# mainboard_motor_v1_4.net
KiCad netlist of a schematic drawn in Altium Designer
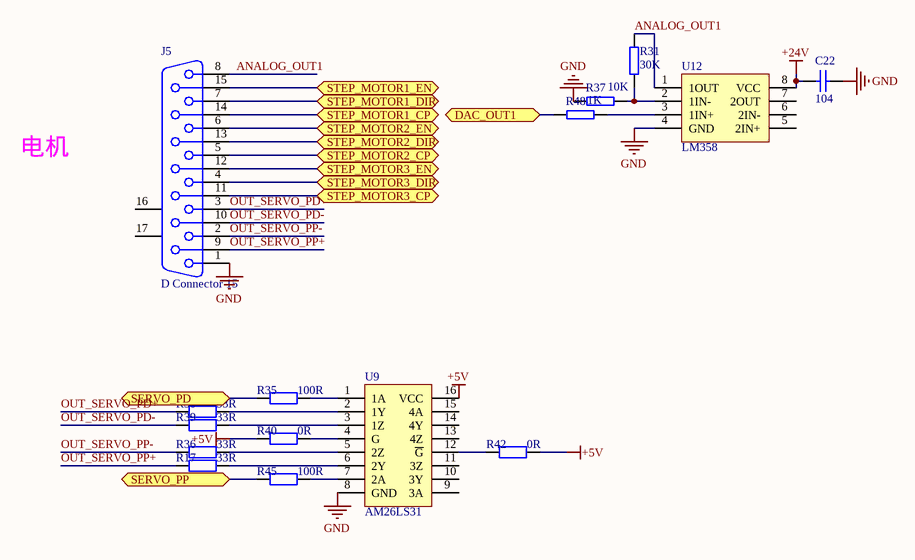
[diagram p0: mainboard_motor.v1.4.SchDoc]

(export (version "E")
  (design (tool "Eeschema 10.0.6"))
  (components
    (comp (ref "C22")
      (value "104")
      (footprint "0805")
      (description "Capacitor")
      (fields (field (name "PUBLISHER") "Altium Limited"))
      (libsource (lib "TIAN's Schlib") (part "Cap"))
    )
    (comp (ref "J5")
      (value "D Connector 15")
      (footprint "DSUB1.385-2H15")
      (description "Receptacle Assembly, 15 Position, Right Angle")
      (fields (field (name "PUBLISHER") "Altium Limited"))
      (libsource (lib "Miscellaneous Connectors") (part "D Connector 15"))
    )
    (comp (ref "R17")
      (value "33R")
      (footprint "0805")
      (description "Resistor")
      (fields (field (name "PUBLISHER") "Altium Limited"))
      (libsource (lib "TIAN's Schlib") (part "Res2"))
    )
    (comp (ref "R31")
      (value "30K")
      (footprint "0805")
      (description "电阻")
      (libsource (lib "Component") (part "RES"))
    )
    (comp (ref "R35")
      (value "100R")
      (footprint "0805")
      (description "Resistor")
      (fields (field (name "PUBLISHER") "Altium Limited"))
      (libsource (lib "TIAN's Schlib") (part "Res2"))
    )
    (comp (ref "R36")
      (value "33R")
      (footprint "0805")
      (description "Resistor")
      (fields (field (name "PUBLISHER") "Altium Limited"))
      (libsource (lib "TIAN's Schlib") (part "Res2"))
    )
    (comp (ref "R37")
      (value "10K")
      (footprint "0805")
      (description "电阻")
      (libsource (lib "Component") (part "RES"))
    )
    (comp (ref "R38")
      (value "33R")
      (footprint "0805")
      (description "Resistor")
      (fields (field (name "PUBLISHER") "Altium Limited"))
      (libsource (lib "TIAN's Schlib") (part "Res2"))
    )
    (comp (ref "R39")
      (value "33R")
      (footprint "0805")
      (description "Resistor")
      (fields (field (name "PUBLISHER") "Altium Limited"))
      (libsource (lib "TIAN's Schlib") (part "Res2"))
    )
    (comp (ref "R40")
      (value "0R")
      (footprint "0805")
      (description "Resistor")
      (fields (field (name "PUBLISHER") "Altium Limited"))
      (libsource (lib "TIAN's Schlib") (part "Res2"))
    )
    (comp (ref "R42")
      (value "0R")
      (footprint "0805")
      (description "Resistor")
      (fields (field (name "PUBLISHER") "Altium Limited"))
      (libsource (lib "TIAN's Schlib") (part "Res2"))
    )
    (comp (ref "R45")
      (value "100R")
      (footprint "0805")
      (description "Resistor")
      (fields (field (name "PUBLISHER") "Altium Limited"))
      (libsource (lib "TIAN's Schlib") (part "Res2"))
    )
    (comp (ref "R48")
      (value "1K")
      (footprint "0805")
      (description "电阻")
      (libsource (lib "Component") (part "RES"))
    )
    (comp (ref "U9") (value "AM26LS31") (footprint "SO-16") (libsource (lib "Chip") (part "AM26LS31")))
    (comp (ref "U12") (value "LM358") (footprint "SO-8") (libsource (lib "Chip") (part "LM358")))
  )
  (nets
    (net (code "1") (name "+5V") (class "Default")
      (node (ref "R40") (pin "2") (pinfunction "2_2") (pintype "passive"))
      (node (ref "R42") (pin "1") (pinfunction "1_1") (pintype "passive"))
      (node (ref "U9") (pin "16") (pinfunction "VCC_16") (pintype "passive"))
    )
    (net (code "2") (name "+24V") (class "Default")
      (node (ref "C22") (pin "2") (pinfunction "2_2") (pintype "passive"))
      (node (ref "U12") (pin "8") (pinfunction "VCC_8") (pintype "passive"))
    )
    (net (code "3") (name "/ANALOG_OUT1") (class "Default")
      (node (ref "J5") (pin "8") (pinfunction "8_8") (pintype "passive"))
      (node (ref "R31") (pin "1") (pinfunction "1_1") (pintype "passive"))
      (node (ref "U12") (pin "1") (pinfunction "1OUT_1") (pintype "passive"))
    )
    (net (code "4") (name "/DAC_OUT1") (class "Default")
      (node (ref "R48") (pin "2") (pinfunction "2_2") (pintype "passive"))
    )
    (net (code "5") (name "/OUT_SERVO_PD+") (class "Default")
      (node (ref "J5") (pin "3") (pinfunction "3_3") (pintype "passive"))
      (node (ref "R38") (pin "2") (pinfunction "2_2") (pintype "passive"))
    )
    (net (code "6") (name "/OUT_SERVO_PD-") (class "Default")
      (node (ref "J5") (pin "10") (pinfunction "10_10") (pintype "passive"))
      (node (ref "R39") (pin "2") (pinfunction "2_2") (pintype "passive"))
    )
    (net (code "7") (name "/OUT_SERVO_PP+") (class "Default")
      (node (ref "J5") (pin "9") (pinfunction "9_9") (pintype "passive"))
      (node (ref "R17") (pin "2") (pinfunction "2_2") (pintype "passive"))
    )
    (net (code "8") (name "/OUT_SERVO_PP-") (class "Default")
      (node (ref "J5") (pin "2") (pinfunction "2_2") (pintype "passive"))
      (node (ref "R36") (pin "2") (pinfunction "2_2") (pintype "passive"))
    )
    (net (code "9") (name "/SERVO_PD") (class "Default")
      (node (ref "R35") (pin "2") (pinfunction "2_2") (pintype "passive"))
    )
    (net (code "10") (name "/SERVO_PP") (class "Default")
      (node (ref "R45") (pin "2") (pinfunction "2_2") (pintype "passive"))
    )
    (net (code "11") (name "/STEP_MOTOR1_CP") (class "Default")
      (node (ref "J5") (pin "14") (pinfunction "14_14") (pintype "passive"))
    )
    (net (code "12") (name "/STEP_MOTOR1_DIR") (class "Default")
      (node (ref "J5") (pin "7") (pinfunction "7_7") (pintype "passive"))
    )
    (net (code "13") (name "/STEP_MOTOR1_EN") (class "Default")
      (node (ref "J5") (pin "15") (pinfunction "15_15") (pintype "passive"))
    )
    (net (code "14") (name "/STEP_MOTOR2_CP") (class "Default")
      (node (ref "J5") (pin "5") (pinfunction "5_5") (pintype "passive"))
    )
    (net (code "15") (name "/STEP_MOTOR2_DIR") (class "Default")
      (node (ref "J5") (pin "13") (pinfunction "13_13") (pintype "passive"))
    )
    (net (code "16") (name "/STEP_MOTOR2_EN") (class "Default")
      (node (ref "J5") (pin "6") (pinfunction "6_6") (pintype "passive"))
    )
    (net (code "17") (name "/STEP_MOTOR3_CP") (class "Default")
      (node (ref "J5") (pin "11") (pinfunction "11_11") (pintype "passive"))
    )
    (net (code "18") (name "/STEP_MOTOR3_DIR") (class "Default")
      (node (ref "J5") (pin "4") (pinfunction "4_4") (pintype "passive"))
    )
    (net (code "19") (name "/STEP_MOTOR3_EN") (class "Default")
      (node (ref "J5") (pin "12") (pinfunction "12_12") (pintype "passive"))
    )
    (net (code "20") (name "GND") (class "Default")
      (node (ref "C22") (pin "1") (pinfunction "1_1") (pintype "passive"))
      (node (ref "J5") (pin "1") (pinfunction "1_1") (pintype "passive"))
      (node (ref "R37") (pin "2") (pinfunction "2_2") (pintype "passive"))
      (node (ref "U12") (pin "4") (pinfunction "GND_4") (pintype "passive"))
      (node (ref "U9") (pin "8") (pinfunction "GND_8") (pintype "passive"))
    )
    (net (code "21") (name "Net-(U9-1A)") (class "Default")
      (node (ref "R35") (pin "1") (pinfunction "1_1") (pintype "passive"))
      (node (ref "U9") (pin "1") (pinfunction "1A_1") (pintype "passive"))
    )
    (net (code "22") (name "Net-(U9-1Y)") (class "Default")
      (node (ref "R38") (pin "1") (pinfunction "1_1") (pintype "passive"))
      (node (ref "U9") (pin "2") (pinfunction "1Y_2") (pintype "passive"))
    )
    (net (code "23") (name "Net-(U9-1Z)") (class "Default")
      (node (ref "R39") (pin "1") (pinfunction "1_1") (pintype "passive"))
      (node (ref "U9") (pin "3") (pinfunction "1Z_3") (pintype "passive"))
    )
    (net (code "24") (name "Net-(U9-2A)") (class "Default")
      (node (ref "R45") (pin "1") (pinfunction "1_1") (pintype "passive"))
      (node (ref "U9") (pin "7") (pinfunction "2A_7") (pintype "passive"))
    )
    (net (code "25") (name "Net-(U9-2Y)") (class "Default")
      (node (ref "R17") (pin "1") (pinfunction "1_1") (pintype "passive"))
      (node (ref "U9") (pin "6") (pinfunction "2Y_6") (pintype "passive"))
    )
    (net (code "26") (name "Net-(U9-2Z)") (class "Default")
      (node (ref "R36") (pin "1") (pinfunction "1_1") (pintype "passive"))
      (node (ref "U9") (pin "5") (pinfunction "2Z_5") (pintype "passive"))
    )
    (net (code "27") (name "Net-(U9-G)") (class "Default")
      (node (ref "R40") (pin "1") (pinfunction "1_1") (pintype "passive"))
      (node (ref "U9") (pin "4") (pinfunction "G_4") (pintype "passive"))
    )
    (net (code "28") (name "Net-(U9-~{G})") (class "Default")
      (node (ref "R42") (pin "2") (pinfunction "2_2") (pintype "passive"))
      (node (ref "U9") (pin "12") (pinfunction "~{G}_12") (pintype "passive"))
    )
    (net (code "29") (name "Net-(U12-1IN+)") (class "Default")
      (node (ref "R48") (pin "1") (pinfunction "1_1") (pintype "passive"))
      (node (ref "U12") (pin "3") (pinfunction "1IN+_3") (pintype "passive"))
    )
    (net (code "30") (name "Net-(U12-1IN-)") (class "Default")
      (node (ref "R31") (pin "2") (pinfunction "2_2") (pintype "passive"))
      (node (ref "R37") (pin "1") (pinfunction "1_1") (pintype "passive"))
      (node (ref "U12") (pin "2") (pinfunction "1IN-_2") (pintype "passive"))
    )
    (net (code "31") (name "unconnected-(J5-MH1-Pad16)") (class "Default")
      (node (ref "J5") (pin "16") (pinfunction "MH1_16") (pintype "passive"))
    )
    (net (code "32") (name "unconnected-(J5-MH2-Pad17)") (class "Default")
      (node (ref "J5") (pin "17") (pinfunction "MH2_17") (pintype "passive"))
    )
    (net (code "33") (name "unconnected-(U9-3A-Pad9)") (class "Default")
      (node (ref "U9") (pin "9") (pinfunction "3A_9") (pintype "passive"))
    )
    (net (code "34") (name "unconnected-(U9-3Y-Pad10)") (class "Default")
      (node (ref "U9") (pin "10") (pinfunction "3Y_10") (pintype "passive"))
    )
    (net (code "35") (name "unconnected-(U9-3Z-Pad11)") (class "Default")
      (node (ref "U9") (pin "11") (pinfunction "3Z_11") (pintype "passive"))
    )
    (net (code "36") (name "unconnected-(U9-4A-Pad15)") (class "Default")
      (node (ref "U9") (pin "15") (pinfunction "4A_15") (pintype "passive"))
    )
    (net (code "37") (name "unconnected-(U9-4Y-Pad14)") (class "Default")
      (node (ref "U9") (pin "14") (pinfunction "4Y_14") (pintype "passive"))
    )
    (net (code "38") (name "unconnected-(U9-4Z-Pad13)") (class "Default")
      (node (ref "U9") (pin "13") (pinfunction "4Z_13") (pintype "passive"))
    )
    (net (code "39") (name "unconnected-(U12-2IN+-Pad5)") (class "Default")
      (node (ref "U12") (pin "5") (pinfunction "2IN+_5") (pintype "passive"))
    )
    (net (code "40") (name "unconnected-(U12-2IN--Pad6)") (class "Default")
      (node (ref "U12") (pin "6") (pinfunction "2IN-_6") (pintype "passive"))
    )
    (net (code "41") (name "unconnected-(U12-2OUT-Pad7)") (class "Default")
      (node (ref "U12") (pin "7") (pinfunction "2OUT_7") (pintype "passive"))
    )
  )
)
